# 4b_-_Latching_IMD.net
KiCad netlist of a schematic drawn in Altium Designer
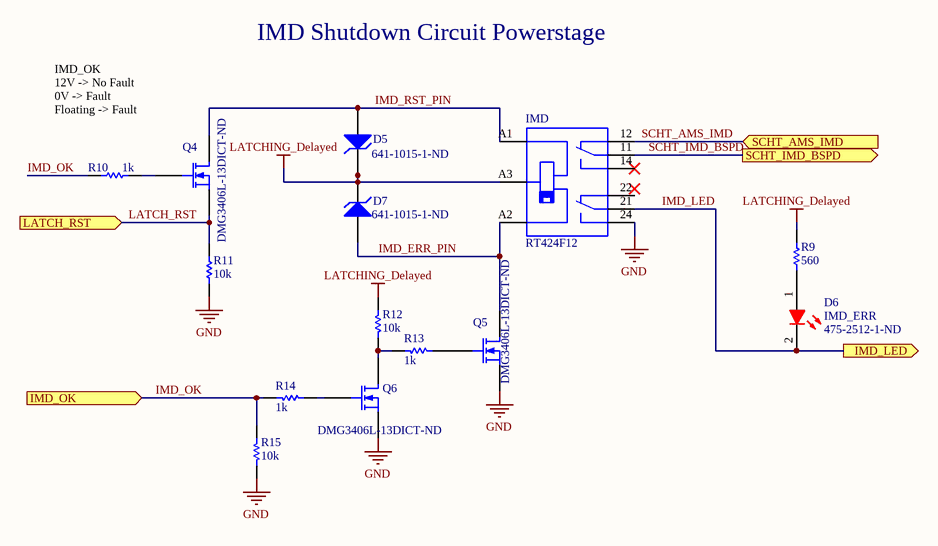
[diagram p0: 4b - Latching IMD.SchDoc]

(export (version "E")
  (design (tool "Eeschema 10.0.6"))
  (components
    (comp (ref "D5")
      (value "D Zener")
      (footprint "DO214AC")
      (description "Zener Diode")
      (fields
        (field (name "SUPPLIER PART NUMBER 1") "641-1015-1-ND")
        (field (name "PUBLISHER") "Altium Limited")
      )
      (libsource (lib "Miscellaneous Devices") (part "D Zener"))
    )
    (comp (ref "D6")
      (value "IMD_ERR")
      (footprint "TOSH-0603LED_RED_V")
      (description "LED, Red 0603 (1608) 63mCd")
      (fields
        (field (name "MANUFACTURER") "Toshiba")
        (field (name "PARTNUMBER") "TLSU1008A(T04)")
        (field (name "SUPPLIER PART NUMBER 1") "475-2512-1-ND")
      )
      (libsource (lib "Altium Content Vault") (part "CMP-0444-00001-1"))
    )
    (comp (ref "D7")
      (value "D Zener")
      (footprint "DO214AC")
      (description "Zener Diode")
      (fields
        (field (name "SUPPLIER PART NUMBER 1") "641-1015-1-ND")
        (field (name "PUBLISHER") "Altium Limited")
      )
      (libsource (lib "Miscellaneous Devices") (part "D Zener"))
    )
    (comp (ref "IMD")
      (value "RT424F12")
      (footprint "TE_5-1393243-4")
      (description "General Purpose Relay DPDT (2 Form C) 12VDC Coil Through Hole")
      (fields (field (name "MF") "TE Connectivity"))
      (libsource (lib "RT424F12") (part "RT424F12"))
    )
    (comp (ref "Q4")
      (value "~")
      (footprint "SOT-23_N")
      (description "N-Channel MOSFET")
      (fields
        (field (name "MANUFACTURER") "Infineon Technologies")
        (field (name "SUPPLIER PART NUMBER 1") "DMG3406L-13DICT-ND")
        (field (name "PUBLISHER") "Altium Limited")
      )
      (libsource (lib "Miscellaneous Devices") (part "MOSFET-N"))
    )
    (comp (ref "Q5")
      (value "~")
      (footprint "SOT-23_N")
      (description "N-Channel MOSFET")
      (fields
        (field (name "MANUFACTURER") "Infineon Technologies")
        (field (name "SUPPLIER PART NUMBER 1") "DMG3406L-13DICT-ND")
        (field (name "PUBLISHER") "Altium Limited")
      )
      (libsource (lib "Miscellaneous Devices") (part "MOSFET-N"))
    )
    (comp (ref "Q6")
      (value "~")
      (footprint "SOT-23_N")
      (description "N-Channel MOSFET")
      (fields
        (field (name "MANUFACTURER") "Infineon Technologies")
        (field (name "SUPPLIER PART NUMBER 1") "DMG3406L-13DICT-ND")
        (field (name "PUBLISHER") "Altium Limited")
      )
      (libsource (lib "Miscellaneous Devices") (part "MOSFET-N"))
    )
    (comp (ref "R9")
      (value "560")
      (footprint "RESC0603(1608)_L")
      (description "0603 (1608 Metric) Chip Resistor")
      (libsource (lib "Altium Content Vault") (part "RES_3"))
    )
    (comp (ref "R10")
      (value "1k")
      (footprint "1608[0603]")
      (description "RES SMD 100 OHM 5% 1/4W 0603")
      (fields
        (field (name "MANUFACTURER") "Rohm Semiconductor")
        (field (name "MANUFACTURER PART NUMBER") "ESR03EZPJ101")
        (field (name "PUBLISHER") "Altium Limited")
      )
      (libsource (lib "Miscellaneous Devices") (part "Res1"))
    )
    (comp (ref "R11")
      (value "10k")
      (footprint "1608[0603]")
      (description "RES SMD 10K OHM 5% 1/4W 0603")
      (fields
        (field (name "MANUFACTURER") "Rohm Semiconductor")
        (field (name "MANUFACTURER PART NUMBER") "ESR03EZPJ103")
        (field (name "PUBLISHER") "Altium Limited")
      )
      (libsource (lib "Miscellaneous Devices") (part "Res1"))
    )
    (comp (ref "R12")
      (value "RHM1.0KDCT-ND")
      (footprint "1608[0603]")
      (description "RES SMD 1.0K OHM 5% 1/4W 0603")
      (fields
        (field (name "MANUFACTURER") "Rohm Semiconductor")
        (field (name "MANUFACTURER PART NUMBER") "ESR03EZPJ102")
        (field (name "RESISTANCE (OHMS)") "10k")
      )
      (libsource (lib "Miscellaneous Devices") (part "Res1"))
    )
    (comp (ref "R13")
      (value "1k")
      (footprint "1608[0603]")
      (description "RES SMD 100 OHM 5% 1/4W 0603")
      (fields
        (field (name "MANUFACTURER") "Rohm Semiconductor")
        (field (name "MANUFACTURER PART NUMBER") "ESR03EZPJ101")
        (field (name "PUBLISHER") "Altium Limited")
      )
      (libsource (lib "Miscellaneous Devices") (part "Res1"))
    )
    (comp (ref "R14")
      (value "1k")
      (footprint "1608[0603]")
      (description "RES SMD 100 OHM 5% 1/4W 0603")
      (fields
        (field (name "MANUFACTURER") "Rohm Semiconductor")
        (field (name "MANUFACTURER PART NUMBER") "ESR03EZPJ101")
        (field (name "PUBLISHER") "Altium Limited")
      )
      (libsource (lib "Miscellaneous Devices") (part "Res1"))
    )
    (comp (ref "R15")
      (value "10k")
      (footprint "1608[0603]")
      (description "RES SMD 2.2K OHM 5% 1/4W 0603")
      (fields
        (field (name "MANUFACTURER") "Rohm Semiconductor")
        (field (name "MANUFACTURER PART NUMBER") "ESR03EZPJ222")
        (field (name "PUBLISHER") "Altium Limited")
      )
      (libsource (lib "Miscellaneous Devices") (part "Res1"))
    )
  )
  (nets
    (net (code "1") (name "/IMD_ERR_PIN") (class "Default")
      (node (ref "D7") (pin "1") (pinfunction "A_1") (pintype "passive"))
      (node (ref "IMD") (pin "A2") (pinfunction "A2_A2") (pintype "passive"))
      (node (ref "Q5") (pin "3") (pinfunction "D_3") (pintype "passive"))
    )
    (net (code "2") (name "/IMD_LED") (class "Default")
      (node (ref "D6") (pin "2") (pinfunction "K_2") (pintype "passive"))
      (node (ref "IMD") (pin "21") (pinfunction "21_21") (pintype "passive"))
    )
    (net (code "3") (name "/IMD_OK") (class "Default")
      (node (ref "R10") (pin "1") (pinfunction "1_1") (pintype "passive"))
      (node (ref "R14") (pin "2") (pinfunction "2_2") (pintype "passive"))
      (node (ref "R15") (pin "1") (pinfunction "1_1") (pintype "passive"))
    )
    (net (code "4") (name "/IMD_RST_PIN") (class "Default")
      (node (ref "D5") (pin "1") (pinfunction "A_1") (pintype "passive"))
      (node (ref "IMD") (pin "A1") (pinfunction "A1_A1") (pintype "passive"))
      (node (ref "Q4") (pin "3") (pinfunction "D_3") (pintype "passive"))
    )
    (net (code "5") (name "/LATCH_RST") (class "Default")
      (node (ref "Q4") (pin "2") (pinfunction "S_2") (pintype "passive"))
      (node (ref "R11") (pin "2") (pinfunction "2_2") (pintype "passive"))
    )
    (net (code "6") (name "/SCHT_AMS_IMD") (class "Default")
      (node (ref "IMD") (pin "12") (pinfunction "12_12") (pintype "passive"))
    )
    (net (code "7") (name "/SCHT_IMD_BSPD") (class "Default")
      (node (ref "IMD") (pin "11") (pinfunction "11_11") (pintype "passive"))
    )
    (net (code "8") (name "GND") (class "Default")
      (node (ref "IMD") (pin "24") (pinfunction "24_24") (pintype "passive"))
      (node (ref "Q5") (pin "2") (pinfunction "S_2") (pintype "passive"))
      (node (ref "Q6") (pin "2") (pinfunction "S_2") (pintype "passive"))
      (node (ref "R11") (pin "1") (pinfunction "1_1") (pintype "passive"))
      (node (ref "R15") (pin "2") (pinfunction "2_2") (pintype "passive"))
    )
    (net (code "9") (name "LATCHING_Delayed") (class "Default")
      (node (ref "D5") (pin "2") (pinfunction "K_2") (pintype "passive"))
      (node (ref "D7") (pin "2") (pinfunction "K_2") (pintype "passive"))
      (node (ref "IMD") (pin "A3") (pinfunction "A3_A3") (pintype "passive"))
      (node (ref "R12") (pin "1") (pinfunction "1_1") (pintype "passive"))
      (node (ref "R9") (pin "2") (pinfunction "2_2") (pintype "passive"))
    )
    (net (code "10") (name "Net-(D6-A)") (class "Default")
      (node (ref "D6") (pin "1") (pinfunction "A_1") (pintype "passive"))
      (node (ref "R9") (pin "1") (pinfunction "1_1") (pintype "passive"))
    )
    (net (code "11") (name "Net-(Q4-G)") (class "Default")
      (node (ref "Q4") (pin "1") (pinfunction "G_1") (pintype "passive"))
      (node (ref "R10") (pin "2") (pinfunction "2_2") (pintype "passive"))
    )
    (net (code "12") (name "Net-(Q5-G)") (class "Default")
      (node (ref "Q5") (pin "1") (pinfunction "G_1") (pintype "passive"))
      (node (ref "R13") (pin "1") (pinfunction "1_1") (pintype "passive"))
    )
    (net (code "13") (name "Net-(Q6-D)") (class "Default")
      (node (ref "Q6") (pin "3") (pinfunction "D_3") (pintype "passive"))
      (node (ref "R12") (pin "2") (pinfunction "2_2") (pintype "passive"))
      (node (ref "R13") (pin "2") (pinfunction "2_2") (pintype "passive"))
    )
    (net (code "14") (name "Net-(Q6-G)") (class "Default")
      (node (ref "Q6") (pin "1") (pinfunction "G_1") (pintype "passive"))
      (node (ref "R14") (pin "1") (pinfunction "1_1") (pintype "passive"))
    )
    (net (code "15") (name "unconnected-(IMD-Pad14)") (class "Default")
      (node (ref "IMD") (pin "14") (pinfunction "14_14") (pintype "passive+no_connect"))
    )
    (net (code "16") (name "unconnected-(IMD-Pad22)") (class "Default")
      (node (ref "IMD") (pin "22") (pinfunction "22_22") (pintype "passive"))
    )
  )
)
